# PowerWaechter.net
KiCad netlist of a schematic drawn in EAGLE
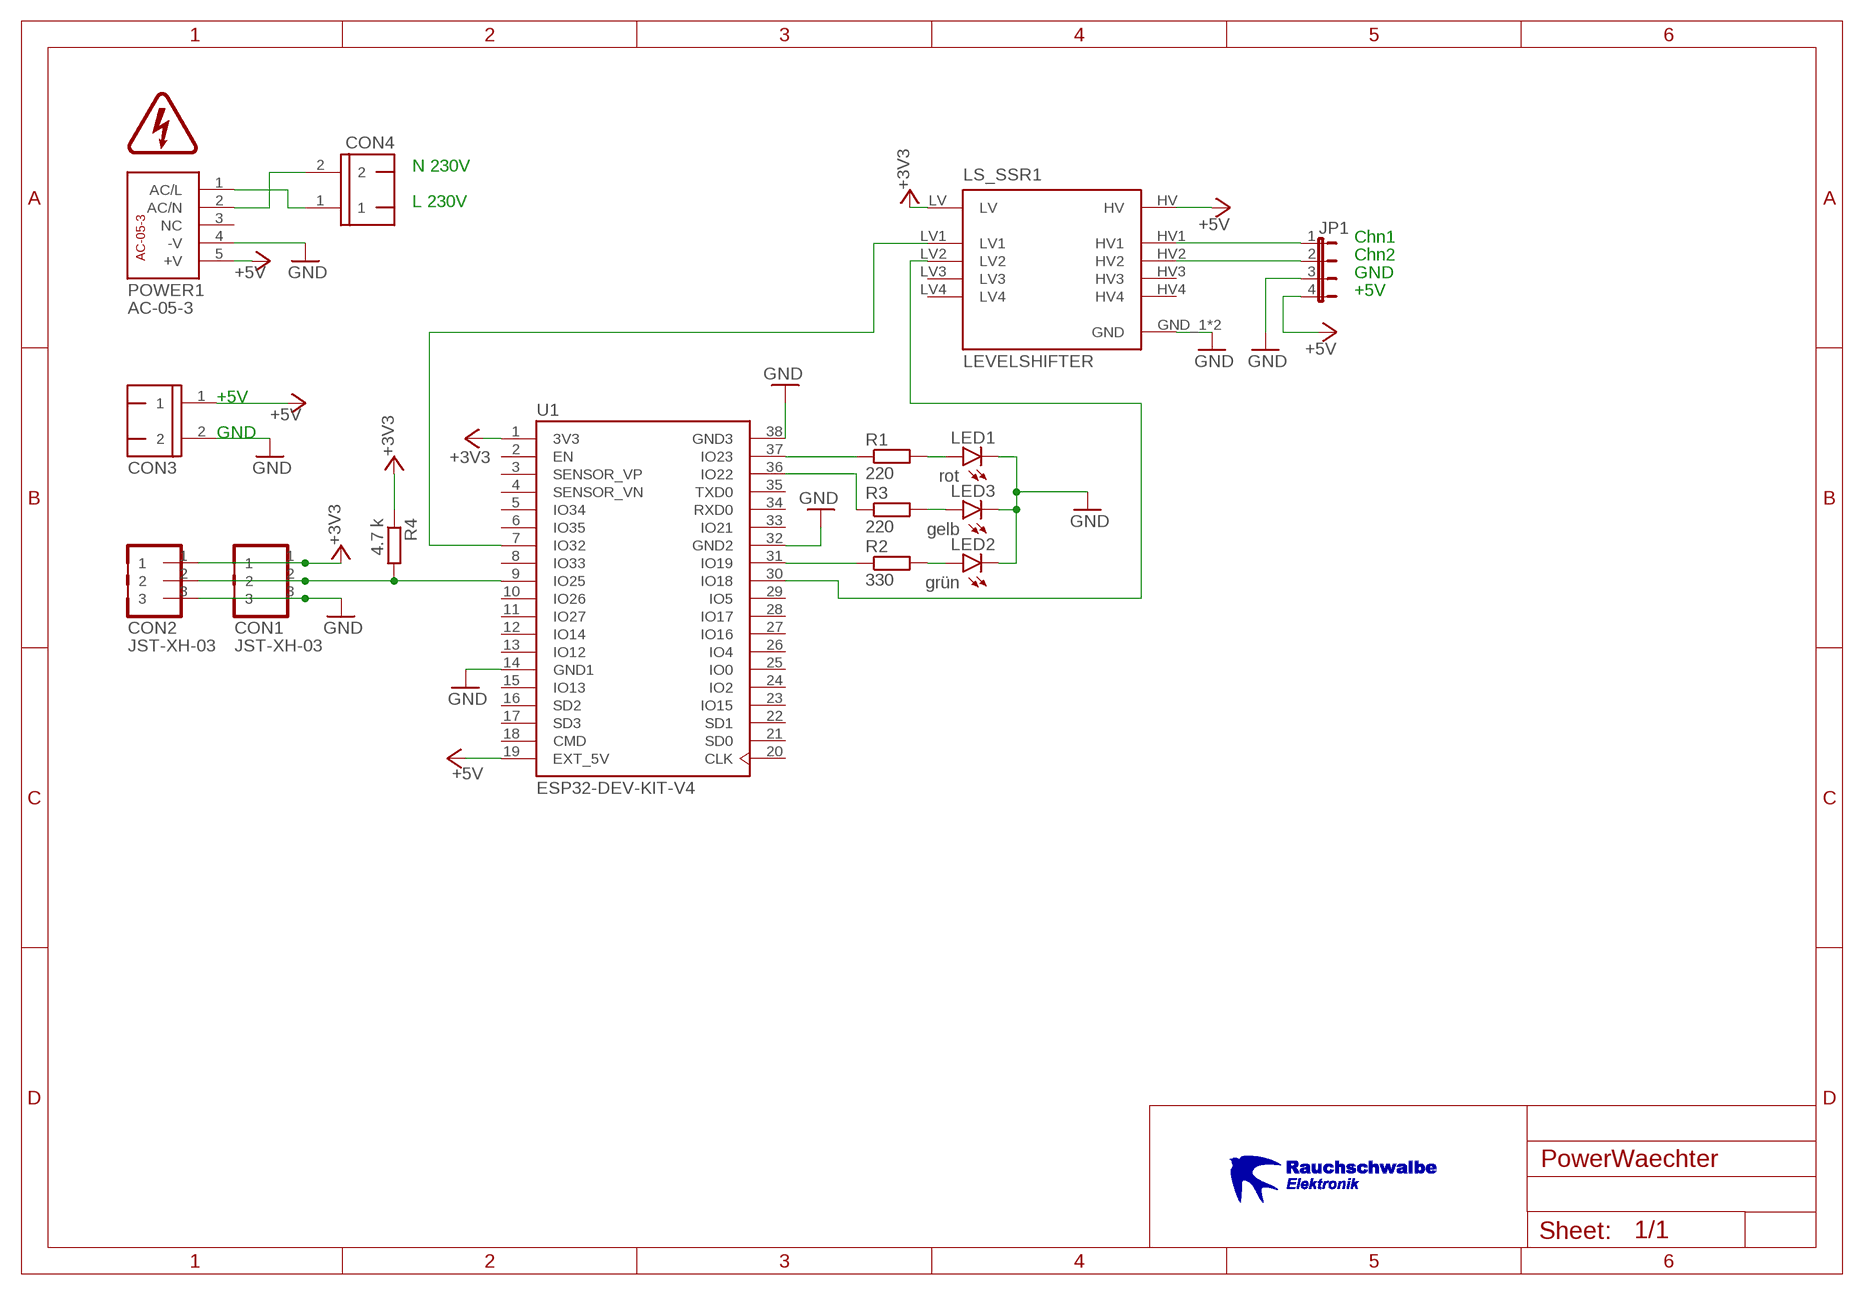
[diagram p0: schematic, sheet 1]

(export (version "E")
  (design (tool "Eeschema 10.0.6"))
  (components
    (comp (ref "CON1")
      (value "JST-XH-03")
      (footprint "eagle-import:JST-XH-03")
      (libsource (lib "eagle-import") (part "JST-XH-03"))
    )
    (comp (ref "CON2")
      (value "JST-XH-03")
      (footprint "eagle-import:JST-XH-03")
      (libsource (lib "eagle-import") (part "JST-XH-03"))
    )
    (comp (ref "CON3")
      (value "WAGO-500-2")
      (footprint "eagle-import:WAGO-500-2")
      (fields (field (name "MPN") "237-102"))
      (libsource (lib "eagle-import") (part "WAGO-500-2"))
    )
    (comp (ref "CON4")
      (value "WAGO-500-2")
      (footprint "eagle-import:WAGO-500-2")
      (fields (field (name "MPN") "237-102"))
      (libsource (lib "eagle-import") (part "WAGO-500-2"))
    )
    (comp (ref "JP1")
      (value "JP4E")
      (footprint "eagle-import:JP4")
      (libsource (lib "eagle-import") (part "JP4E"))
    )
    (comp (ref "LED1")
      (value "rot")
      (footprint "eagle-import:LED3MM")
      (libsource (lib "eagle-import") (part "LED3MM"))
    )
    (comp (ref "LED2")
      (value "grün")
      (footprint "eagle-import:LED3MM")
      (libsource (lib "eagle-import") (part "LED3MM"))
    )
    (comp (ref "LED3")
      (value "gelb")
      (footprint "eagle-import:LED3MM")
      (libsource (lib "eagle-import") (part "LED3MM"))
    )
    (comp (ref "LS_SSR1")
      (value "LEVELSHIFTER")
      (footprint "eagle-import:LEVELSHIFTER")
      (fields (field (name "MF") "SparkFun") (field (name "MP") "BOB-12009"))
      (libsource (lib "eagle-import") (part "LEVELSHIFTER"))
    )
    (comp (ref "POWER1")
      (value "AC-05-3")
      (footprint "eagle-import:AC-05-3")
      (libsource (lib "eagle-import") (part "AC-05-3"))
    )
    (comp (ref "R1")
      (value "220")
      (footprint "eagle-import:0207_10")
      (libsource (lib "eagle-import") (part "R_10MM0207/10"))
    )
    (comp (ref "R2")
      (value "330")
      (footprint "eagle-import:0207_10")
      (libsource (lib "eagle-import") (part "R_10MM0207/10"))
    )
    (comp (ref "R3")
      (value "220")
      (footprint "eagle-import:0207_10")
      (libsource (lib "eagle-import") (part "R_10MM0207/10"))
    )
    (comp (ref "R4")
      (value "4.7 k")
      (footprint "eagle-import:0207_10")
      (libsource (lib "eagle-import") (part "R_10MM0207/10"))
    )
    (comp (ref "U$1")
      (value "WARNLABLE_BLITZ_KLEIN")
      (footprint "eagle-import:WARNLABLE_BLITZ_KLEIN")
      (libsource (lib "eagle-import") (part "WARNLABLE_BLITZ_KLEIN"))
    )
    (comp (ref "U$2")
      (value "LOGO_RAUCHSCHWALBE_KLEIN")
      (footprint "eagle-import:LOGO_RAUCHSCHWALBE_KLEIN")
      (libsource (lib "eagle-import") (part "LOGO_RAUCHSCHWALBE_KLEIN"))
    )
    (comp (ref "U1")
      (value "ESP32-DEV-KIT-V4")
      (footprint "eagle-import:ESP32-DEV-KIT-V4")
      (fields (field (name "MF") "Espressif Systems") (field (name "MP") "ESP32-DEVKITC"))
      (libsource (lib "eagle-import") (part "ESP32-DEV-KIT-V4"))
    )
  )
  (nets
    (net (code "1") (name "+3V3") (class "Default")
      (node (ref "CON1") (pin "1") (pinfunction "1_1") (pintype "passive"))
      (node (ref "CON2") (pin "1") (pinfunction "1_1") (pintype "passive"))
      (node (ref "LS_SSR1") (pin "LV") (pinfunction "LV_LV") (pintype "bidirectional"))
      (node (ref "R4") (pin "1") (pinfunction "1_1") (pintype "passive"))
      (node (ref "U1") (pin "1") (pinfunction "3V3_1") (pintype "power_in"))
    )
    (net (code "2") (name "+5V") (class "Default")
      (node (ref "CON3") (pin "1") (pinfunction "1_1") (pintype "passive"))
      (node (ref "JP1") (pin "4") (pinfunction "4_4") (pintype "passive"))
      (node (ref "LS_SSR1") (pin "HV") (pinfunction "HV_HV") (pintype "bidirectional"))
      (node (ref "POWER1") (pin "5") (pinfunction "+V_5") (pintype "power_in"))
      (node (ref "U1") (pin "19") (pinfunction "EXT_5V_19") (pintype "power_in"))
    )
    (net (code "3") (name "GND") (class "Default")
      (node (ref "CON1") (pin "3") (pinfunction "3_3") (pintype "passive"))
      (node (ref "CON2") (pin "3") (pinfunction "3_3") (pintype "passive"))
      (node (ref "CON3") (pin "2") (pinfunction "2_2") (pintype "passive"))
      (node (ref "JP1") (pin "3") (pinfunction "3_3") (pintype "passive"))
      (node (ref "LED1") (pin "K") (pinfunction "C_K") (pintype "passive"))
      (node (ref "LED2") (pin "K") (pinfunction "C_K") (pintype "passive"))
      (node (ref "LED3") (pin "K") (pinfunction "C_K") (pintype "passive"))
      (node (ref "LS_SSR1") (pin "GND_1") (pinfunction "GND_GND_1") (pintype "power_in"))
      (node (ref "LS_SSR1") (pin "GND_2") (pinfunction "GND_GND_2") (pintype "power_in"))
      (node (ref "POWER1") (pin "4") (pinfunction "-V_4") (pintype "power_in"))
      (node (ref "U1") (pin "14") (pinfunction "GND1_14") (pintype "power_in"))
      (node (ref "U1") (pin "32") (pinfunction "GND2_32") (pintype "power_in"))
      (node (ref "U1") (pin "38") (pinfunction "GND3_38") (pintype "power_in"))
    )
    (net (code "4") (name "Net-(JP1-Pad1)") (class "Default")
      (node (ref "JP1") (pin "1") (pinfunction "1_1") (pintype "passive"))
      (node (ref "LS_SSR1") (pin "HV1") (pinfunction "HV1_HV1") (pintype "bidirectional"))
    )
    (net (code "5") (name "Net-(JP1-Pad2)") (class "Default")
      (node (ref "JP1") (pin "2") (pinfunction "2_2") (pintype "passive"))
      (node (ref "LS_SSR1") (pin "HV2") (pinfunction "HV2_HV2") (pintype "bidirectional"))
    )
    (net (code "6") (name "Net-(LED1-PadA)") (class "Default")
      (node (ref "LED1") (pin "A") (pinfunction "A_A") (pintype "passive"))
      (node (ref "R1") (pin "2") (pinfunction "2_2") (pintype "passive"))
    )
    (net (code "7") (name "Net-(LED2-PadA)") (class "Default")
      (node (ref "LED2") (pin "A") (pinfunction "A_A") (pintype "passive"))
      (node (ref "R2") (pin "2") (pinfunction "2_2") (pintype "passive"))
    )
    (net (code "8") (name "Net-(LED3-PadA)") (class "Default")
      (node (ref "LED3") (pin "A") (pinfunction "A_A") (pintype "passive"))
      (node (ref "R3") (pin "2") (pinfunction "2_2") (pintype "passive"))
    )
    (net (code "9") (name "Net-(POWER1-AC{slash}L)") (class "Default")
      (node (ref "CON4") (pin "1") (pinfunction "1_1") (pintype "passive"))
      (node (ref "POWER1") (pin "1") (pinfunction "AC/L_1") (pintype "power_in"))
    )
    (net (code "10") (name "Net-(POWER1-AC{slash}N)") (class "Default")
      (node (ref "CON4") (pin "2") (pinfunction "2_2") (pintype "passive"))
      (node (ref "POWER1") (pin "2") (pinfunction "AC/N_2") (pintype "power_in"))
    )
    (net (code "11") (name "Net-(U1-IO18)") (class "Default")
      (node (ref "LS_SSR1") (pin "LV2") (pinfunction "LV2_LV2") (pintype "bidirectional"))
      (node (ref "U1") (pin "30") (pinfunction "IO18_30") (pintype "bidirectional"))
    )
    (net (code "12") (name "Net-(U1-IO19)") (class "Default")
      (node (ref "R2") (pin "1") (pinfunction "1_1") (pintype "passive"))
      (node (ref "U1") (pin "31") (pinfunction "IO19_31") (pintype "bidirectional"))
    )
    (net (code "13") (name "Net-(U1-IO22)") (class "Default")
      (node (ref "R3") (pin "1") (pinfunction "1_1") (pintype "passive"))
      (node (ref "U1") (pin "36") (pinfunction "IO22_36") (pintype "bidirectional"))
    )
    (net (code "14") (name "Net-(U1-IO23)") (class "Default")
      (node (ref "R1") (pin "1") (pinfunction "1_1") (pintype "passive"))
      (node (ref "U1") (pin "37") (pinfunction "IO23_37") (pintype "bidirectional"))
    )
    (net (code "15") (name "Net-(U1-IO25)") (class "Default")
      (node (ref "CON1") (pin "2") (pinfunction "2_2") (pintype "passive"))
      (node (ref "CON2") (pin "2") (pinfunction "2_2") (pintype "passive"))
      (node (ref "R4") (pin "2") (pinfunction "2_2") (pintype "passive"))
      (node (ref "U1") (pin "9") (pinfunction "IO25_9") (pintype "bidirectional"))
    )
    (net (code "16") (name "Net-(U1-IO32)") (class "Default")
      (node (ref "LS_SSR1") (pin "LV1") (pinfunction "LV1_LV1") (pintype "bidirectional"))
      (node (ref "U1") (pin "7") (pinfunction "IO32_7") (pintype "bidirectional"))
    )
    (net (code "17") (name "unconnected-(LS_SSR1-PadHV3)") (class "Default")
      (node (ref "LS_SSR1") (pin "HV3") (pinfunction "HV3_HV3") (pintype "bidirectional"))
    )
    (net (code "18") (name "unconnected-(LS_SSR1-PadHV4)") (class "Default")
      (node (ref "LS_SSR1") (pin "HV4") (pinfunction "HV4_HV4") (pintype "bidirectional"))
    )
    (net (code "19") (name "unconnected-(LS_SSR1-PadLV3)") (class "Default")
      (node (ref "LS_SSR1") (pin "LV3") (pinfunction "LV3_LV3") (pintype "bidirectional"))
    )
    (net (code "20") (name "unconnected-(LS_SSR1-PadLV4)") (class "Default")
      (node (ref "LS_SSR1") (pin "LV4") (pinfunction "LV4_LV4") (pintype "bidirectional"))
    )
    (net (code "21") (name "unconnected-(POWER1-NC-Pad3)") (class "Default")
      (node (ref "POWER1") (pin "3") (pinfunction "NC_3") (pintype "no_connect"))
    )
    (net (code "22") (name "unconnected-(U1-CLK-Pad20)") (class "Default")
      (node (ref "U1") (pin "20") (pinfunction "CLK_20") (pintype "input"))
    )
    (net (code "23") (name "unconnected-(U1-CMD-Pad18)") (class "Default")
      (node (ref "U1") (pin "18") (pinfunction "CMD_18") (pintype "bidirectional"))
    )
    (net (code "24") (name "unconnected-(U1-EN-Pad2)") (class "Default")
      (node (ref "U1") (pin "2") (pinfunction "EN_2") (pintype "input"))
    )
    (net (code "25") (name "unconnected-(U1-IO0-Pad25)") (class "Default")
      (node (ref "U1") (pin "25") (pinfunction "IO0_25") (pintype "bidirectional"))
    )
    (net (code "26") (name "unconnected-(U1-IO2-Pad24)") (class "Default")
      (node (ref "U1") (pin "24") (pinfunction "IO2_24") (pintype "bidirectional"))
    )
    (net (code "27") (name "unconnected-(U1-IO4-Pad26)") (class "Default")
      (node (ref "U1") (pin "26") (pinfunction "IO4_26") (pintype "bidirectional"))
    )
    (net (code "28") (name "unconnected-(U1-IO5-Pad29)") (class "Default")
      (node (ref "U1") (pin "29") (pinfunction "IO5_29") (pintype "bidirectional"))
    )
    (net (code "29") (name "unconnected-(U1-IO12-Pad13)") (class "Default")
      (node (ref "U1") (pin "13") (pinfunction "IO12_13") (pintype "bidirectional"))
    )
    (net (code "30") (name "unconnected-(U1-IO13-Pad15)") (class "Default")
      (node (ref "U1") (pin "15") (pinfunction "IO13_15") (pintype "bidirectional"))
    )
    (net (code "31") (name "unconnected-(U1-IO14-Pad12)") (class "Default")
      (node (ref "U1") (pin "12") (pinfunction "IO14_12") (pintype "bidirectional"))
    )
    (net (code "32") (name "unconnected-(U1-IO15-Pad23)") (class "Default")
      (node (ref "U1") (pin "23") (pinfunction "IO15_23") (pintype "bidirectional"))
    )
    (net (code "33") (name "unconnected-(U1-IO16-Pad27)") (class "Default")
      (node (ref "U1") (pin "27") (pinfunction "IO16_27") (pintype "bidirectional"))
    )
    (net (code "34") (name "unconnected-(U1-IO17-Pad28)") (class "Default")
      (node (ref "U1") (pin "28") (pinfunction "IO17_28") (pintype "bidirectional"))
    )
    (net (code "35") (name "unconnected-(U1-IO21-Pad33)") (class "Default")
      (node (ref "U1") (pin "33") (pinfunction "IO21_33") (pintype "bidirectional"))
    )
    (net (code "36") (name "unconnected-(U1-IO26-Pad10)") (class "Default")
      (node (ref "U1") (pin "10") (pinfunction "IO26_10") (pintype "bidirectional"))
    )
    (net (code "37") (name "unconnected-(U1-IO27-Pad11)") (class "Default")
      (node (ref "U1") (pin "11") (pinfunction "IO27_11") (pintype "bidirectional"))
    )
    (net (code "38") (name "unconnected-(U1-IO33-Pad8)") (class "Default")
      (node (ref "U1") (pin "8") (pinfunction "IO33_8") (pintype "bidirectional"))
    )
    (net (code "39") (name "unconnected-(U1-IO34-Pad5)") (class "Default")
      (node (ref "U1") (pin "5") (pinfunction "IO34_5") (pintype "bidirectional"))
    )
    (net (code "40") (name "unconnected-(U1-IO35-Pad6)") (class "Default")
      (node (ref "U1") (pin "6") (pinfunction "IO35_6") (pintype "bidirectional"))
    )
    (net (code "41") (name "unconnected-(U1-RXD0-Pad34)") (class "Default")
      (node (ref "U1") (pin "34") (pinfunction "RXD0_34") (pintype "input"))
    )
    (net (code "42") (name "unconnected-(U1-SD0-Pad21)") (class "Default")
      (node (ref "U1") (pin "21") (pinfunction "SD0_21") (pintype "bidirectional"))
    )
    (net (code "43") (name "unconnected-(U1-SD1-Pad22)") (class "Default")
      (node (ref "U1") (pin "22") (pinfunction "SD1_22") (pintype "bidirectional"))
    )
    (net (code "44") (name "unconnected-(U1-SD2-Pad16)") (class "Default")
      (node (ref "U1") (pin "16") (pinfunction "SD2_16") (pintype "bidirectional"))
    )
    (net (code "45") (name "unconnected-(U1-SD3-Pad17)") (class "Default")
      (node (ref "U1") (pin "17") (pinfunction "SD3_17") (pintype "bidirectional"))
    )
    (net (code "46") (name "unconnected-(U1-SENSOR_VN-Pad4)") (class "Default")
      (node (ref "U1") (pin "4") (pinfunction "SENSOR_VN_4") (pintype "input"))
    )
    (net (code "47") (name "unconnected-(U1-SENSOR_VP-Pad3)") (class "Default")
      (node (ref "U1") (pin "3") (pinfunction "SENSOR_VP_3") (pintype "input"))
    )
    (net (code "48") (name "unconnected-(U1-TXD0-Pad35)") (class "Default")
      (node (ref "U1") (pin "35") (pinfunction "TXD0_35") (pintype "output"))
    )
  )
)
